# 130802_AriloRX_0_0.net
KiCad netlist of a schematic drawn in EAGLE
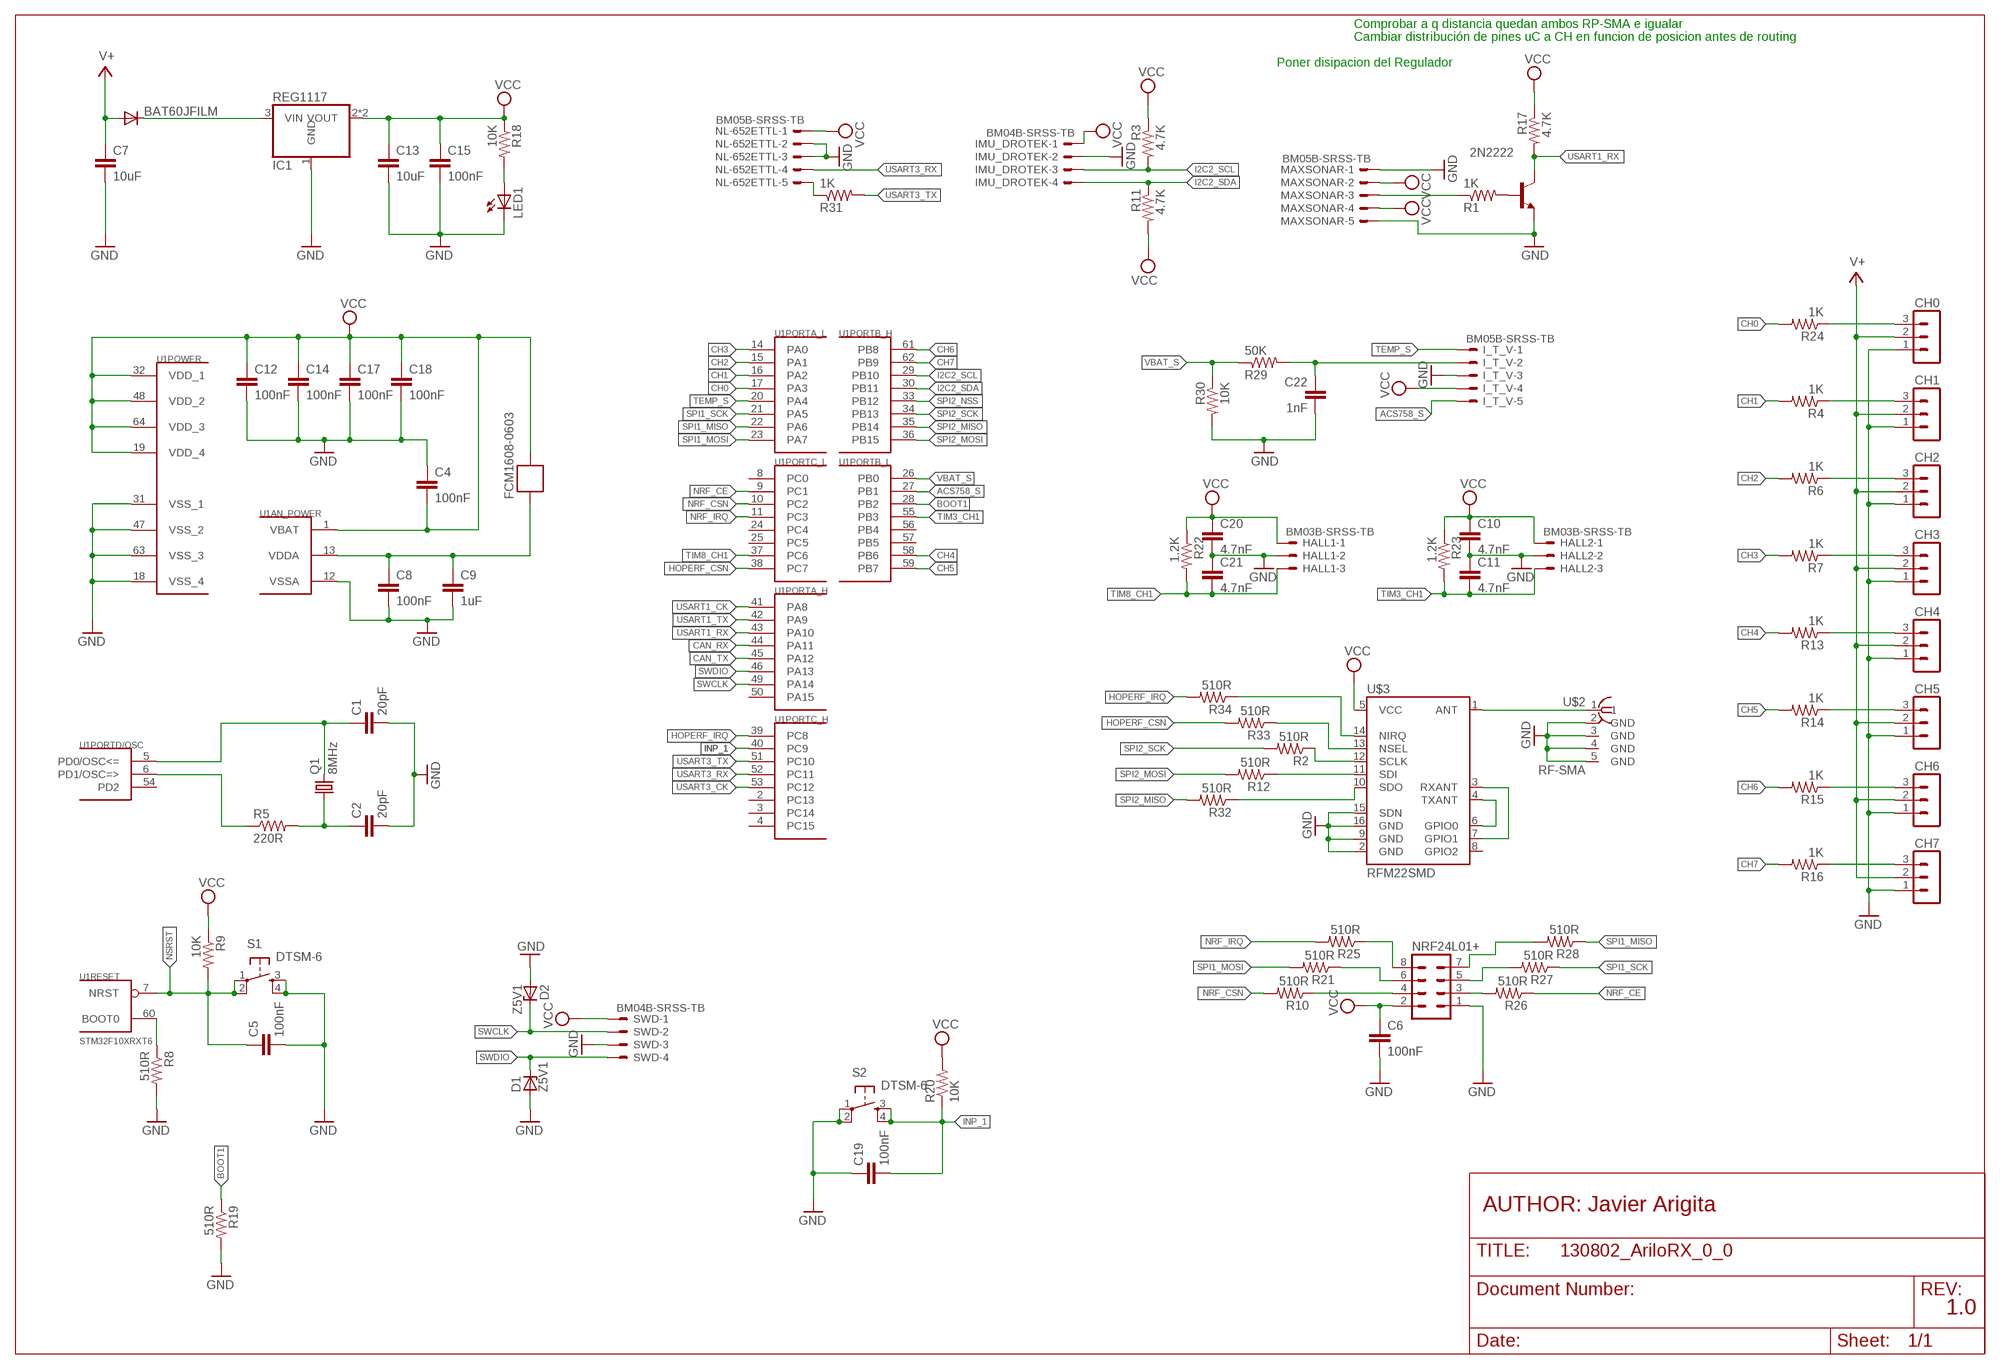
[diagram p0: schematic, sheet 1]

(export (version "E")
  (design (tool "Eeschema 10.0.6"))
  (components
    (comp (ref "2N2222")
      (value "MMBT2222ALT1-NPN-SOT23-BEC")
      (footprint "eagle-import:SOT23-BEC")
      (libsource (lib "eagle-import") (part "-NPN-SOT23-BECMMBT2222ALT1"))
    )
    (comp (ref "BAT60JFILM")
      (value "DIODE-SOD323-R")
      (footprint "eagle-import:SOD323-R")
      (libsource (lib "eagle-import") (part "DIODE-SOD323-R"))
    )
    (comp (ref "C1")
      (value "20pF")
      (footprint "eagle-import:C0805")
      (libsource (lib "eagle-import") (part "C-EUC0805"))
    )
    (comp (ref "C2")
      (value "20pF")
      (footprint "eagle-import:C0805")
      (libsource (lib "eagle-import") (part "C-EUC0805"))
    )
    (comp (ref "C4")
      (value "100nF")
      (footprint "eagle-import:C0805")
      (libsource (lib "eagle-import") (part "C-EUC0805"))
    )
    (comp (ref "C5")
      (value "100nF")
      (footprint "eagle-import:C0805")
      (libsource (lib "eagle-import") (part "C-EUC0805"))
    )
    (comp (ref "C6")
      (value "100nF")
      (footprint "eagle-import:C0805")
      (libsource (lib "eagle-import") (part "C-EUC0805"))
    )
    (comp (ref "C7")
      (value "10uF")
      (footprint "eagle-import:C3216")
      (libsource (lib "eagle-import") (part "resistor_C-EUC3216"))
    )
    (comp (ref "C8")
      (value "100nF")
      (footprint "eagle-import:C0805")
      (libsource (lib "eagle-import") (part "C-EUC0805"))
    )
    (comp (ref "C9")
      (value "1uF")
      (footprint "eagle-import:C3216")
      (libsource (lib "eagle-import") (part "resistor_C-EUC3216"))
    )
    (comp (ref "C10")
      (value "4.7nF")
      (footprint "eagle-import:C0805")
      (libsource (lib "eagle-import") (part "C-EUC0805"))
    )
    (comp (ref "C11")
      (value "4.7nF")
      (footprint "eagle-import:C0805")
      (libsource (lib "eagle-import") (part "C-EUC0805"))
    )
    (comp (ref "C12")
      (value "100nF")
      (footprint "eagle-import:C0805")
      (libsource (lib "eagle-import") (part "C-EUC0805"))
    )
    (comp (ref "C13")
      (value "10uF")
      (footprint "eagle-import:C3216")
      (libsource (lib "eagle-import") (part "resistor_C-EUC3216"))
    )
    (comp (ref "C14")
      (value "100nF")
      (footprint "eagle-import:C0805")
      (libsource (lib "eagle-import") (part "C-EUC0805"))
    )
    (comp (ref "C15")
      (value "100nF")
      (footprint "eagle-import:C0805")
      (libsource (lib "eagle-import") (part "C-EUC0805"))
    )
    (comp (ref "C17")
      (value "100nF")
      (footprint "eagle-import:C0805")
      (libsource (lib "eagle-import") (part "C-EUC0805"))
    )
    (comp (ref "C18")
      (value "100nF")
      (footprint "eagle-import:C0805")
      (libsource (lib "eagle-import") (part "C-EUC0805"))
    )
    (comp (ref "C19")
      (value "100nF")
      (footprint "eagle-import:C0805")
      (libsource (lib "eagle-import") (part "C-EUC0805"))
    )
    (comp (ref "C20")
      (value "4.7nF")
      (footprint "eagle-import:C0805")
      (libsource (lib "eagle-import") (part "C-EUC0805"))
    )
    (comp (ref "C21")
      (value "4.7nF")
      (footprint "eagle-import:C0805")
      (libsource (lib "eagle-import") (part "C-EUC0805"))
    )
    (comp (ref "C22")
      (value "1nF")
      (footprint "eagle-import:C0805")
      (libsource (lib "eagle-import") (part "C-EUC0805"))
    )
    (comp (ref "CH0")
      (value "MA03-1")
      (footprint "eagle-import:MA03-1")
      (libsource (lib "eagle-import") (part "MA03-1"))
    )
    (comp (ref "CH1")
      (value "MA03-1")
      (footprint "eagle-import:MA03-1")
      (libsource (lib "eagle-import") (part "MA03-1"))
    )
    (comp (ref "CH2")
      (value "MA03-1")
      (footprint "eagle-import:MA03-1")
      (libsource (lib "eagle-import") (part "MA03-1"))
    )
    (comp (ref "CH3")
      (value "MA03-1")
      (footprint "eagle-import:MA03-1")
      (libsource (lib "eagle-import") (part "MA03-1"))
    )
    (comp (ref "CH4")
      (value "MA03-1")
      (footprint "eagle-import:MA03-1")
      (libsource (lib "eagle-import") (part "MA03-1"))
    )
    (comp (ref "CH5")
      (value "MA03-1")
      (footprint "eagle-import:MA03-1")
      (libsource (lib "eagle-import") (part "MA03-1"))
    )
    (comp (ref "CH6")
      (value "MA03-1")
      (footprint "eagle-import:MA03-1")
      (libsource (lib "eagle-import") (part "MA03-1"))
    )
    (comp (ref "CH7")
      (value "MA03-1")
      (footprint "eagle-import:MA03-1")
      (libsource (lib "eagle-import") (part "MA03-1"))
    )
    (comp (ref "D1")
      (value "Z5V1")
      (footprint "eagle-import:SOD80C")
      (libsource (lib "eagle-import") (part "ZENER-DIODESOD80C"))
    )
    (comp (ref "D2")
      (value "Z5V1")
      (footprint "eagle-import:SOD80C")
      (libsource (lib "eagle-import") (part "ZENER-DIODESOD80C"))
    )
    (comp (ref "FCM1608-0603")
      (value "FERRITE-BEAD")
      (footprint "eagle-import:R0603")
      (libsource (lib "eagle-import") (part "FERRITE-BEAD"))
    )
    (comp (ref "HALL1")
      (value "BM03B-SRSS-TB")
      (footprint "eagle-import:BM03B-SRSS-TB")
      (libsource (lib "eagle-import") (part "?M03B-SRSS-TBB"))
    )
    (comp (ref "HALL2")
      (value "BM03B-SRSS-TB")
      (footprint "eagle-import:BM03B-SRSS-TB")
      (libsource (lib "eagle-import") (part "?M03B-SRSS-TBB"))
    )
    (comp (ref "IC1")
      (value "REG1117")
      (footprint "eagle-import:SOT223")
      (libsource (lib "eagle-import") (part "REG1117"))
    )
    (comp (ref "IMU_DROTEK")
      (value "BM04B-SRSS-TB")
      (footprint "eagle-import:BM04B-SRSS-TB")
      (libsource (lib "eagle-import") (part "?M04B-SRSS-TBB"))
    )
    (comp (ref "I_T_V")
      (value "BM05B-SRSS-TB")
      (footprint "eagle-import:BM05B-SRSS-TB")
      (libsource (lib "eagle-import") (part "?M05B-SRSS-TBB"))
    )
    (comp (ref "LED1")
      (value "LED0805")
      (footprint "eagle-import:CHIPLED_0805")
      (libsource (lib "eagle-import") (part "LED0805"))
    )
    (comp (ref "MAXSONAR")
      (value "BM05B-SRSS-TB")
      (footprint "eagle-import:BM05B-SRSS-TB")
      (libsource (lib "eagle-import") (part "?M05B-SRSS-TBB"))
    )
    (comp (ref "NL-652ETTL")
      (value "BM05B-SRSS-TB")
      (footprint "eagle-import:BM05B-SRSS-TB")
      (libsource (lib "eagle-import") (part "?M05B-SRSS-TBB"))
    )
    (comp (ref "NRF24L01+")
      (value "MA04-2")
      (footprint "eagle-import:MA04-2")
      (libsource (lib "eagle-import") (part "MA04-2"))
    )
    (comp (ref "Q1")
      (value "8MHz")
      (footprint "eagle-import:SM49")
      (libsource (lib "eagle-import") (part "CRYSTALSM49"))
    )
    (comp (ref "R1")
      (value "1K")
      (footprint "eagle-import:R0805")
      (libsource (lib "eagle-import") (part "RESISTOR0805"))
    )
    (comp (ref "R2")
      (value "510R")
      (footprint "eagle-import:R0805")
      (libsource (lib "eagle-import") (part "RESISTOR0805"))
    )
    (comp (ref "R3")
      (value "4.7K")
      (footprint "eagle-import:R0805")
      (libsource (lib "eagle-import") (part "RESISTOR0805"))
    )
    (comp (ref "R4")
      (value "1K")
      (footprint "eagle-import:R0805")
      (libsource (lib "eagle-import") (part "RESISTOR0805"))
    )
    (comp (ref "R5")
      (value "220R")
      (footprint "eagle-import:R0805")
      (libsource (lib "eagle-import") (part "RESISTOR0805"))
    )
    (comp (ref "R6")
      (value "1K")
      (footprint "eagle-import:R0805")
      (libsource (lib "eagle-import") (part "RESISTOR0805"))
    )
    (comp (ref "R7")
      (value "1K")
      (footprint "eagle-import:R0805")
      (libsource (lib "eagle-import") (part "RESISTOR0805"))
    )
    (comp (ref "R8")
      (value "510R")
      (footprint "eagle-import:R0805")
      (libsource (lib "eagle-import") (part "RESISTOR0805"))
    )
    (comp (ref "R9")
      (value "10K")
      (footprint "eagle-import:R0805")
      (libsource (lib "eagle-import") (part "RESISTOR0805"))
    )
    (comp (ref "R10")
      (value "510R")
      (footprint "eagle-import:R0805")
      (libsource (lib "eagle-import") (part "RESISTOR0805"))
    )
    (comp (ref "R11")
      (value "4.7K")
      (footprint "eagle-import:R0805")
      (libsource (lib "eagle-import") (part "RESISTOR0805"))
    )
    (comp (ref "R12")
      (value "510R")
      (footprint "eagle-import:R0805")
      (libsource (lib "eagle-import") (part "RESISTOR0805"))
    )
    (comp (ref "R13")
      (value "1K")
      (footprint "eagle-import:R0805")
      (libsource (lib "eagle-import") (part "RESISTOR0805"))
    )
    (comp (ref "R14")
      (value "1K")
      (footprint "eagle-import:R0805")
      (libsource (lib "eagle-import") (part "RESISTOR0805"))
    )
    (comp (ref "R15")
      (value "1K")
      (footprint "eagle-import:R0805")
      (libsource (lib "eagle-import") (part "RESISTOR0805"))
    )
    (comp (ref "R16")
      (value "1K")
      (footprint "eagle-import:R0805")
      (libsource (lib "eagle-import") (part "RESISTOR0805"))
    )
    (comp (ref "R17")
      (value "4.7K")
      (footprint "eagle-import:R0805")
      (libsource (lib "eagle-import") (part "RESISTOR0805"))
    )
    (comp (ref "R18")
      (value "10K")
      (footprint "eagle-import:R0805")
      (libsource (lib "eagle-import") (part "RESISTOR0805"))
    )
    (comp (ref "R19")
      (value "510R")
      (footprint "eagle-import:R0805")
      (libsource (lib "eagle-import") (part "RESISTOR0805"))
    )
    (comp (ref "R20")
      (value "10K")
      (footprint "eagle-import:R0805")
      (libsource (lib "eagle-import") (part "RESISTOR0805"))
    )
    (comp (ref "R21")
      (value "510R")
      (footprint "eagle-import:R0805")
      (libsource (lib "eagle-import") (part "RESISTOR0805"))
    )
    (comp (ref "R22")
      (value "1.2K")
      (footprint "eagle-import:R0805")
      (libsource (lib "eagle-import") (part "RESISTOR0805"))
    )
    (comp (ref "R23")
      (value "1.2K")
      (footprint "eagle-import:R0805")
      (libsource (lib "eagle-import") (part "RESISTOR0805"))
    )
    (comp (ref "R24")
      (value "1K")
      (footprint "eagle-import:R0805")
      (libsource (lib "eagle-import") (part "RESISTOR0805"))
    )
    (comp (ref "R25")
      (value "510R")
      (footprint "eagle-import:R0805")
      (libsource (lib "eagle-import") (part "RESISTOR0805"))
    )
    (comp (ref "R26")
      (value "510R")
      (footprint "eagle-import:R0805")
      (libsource (lib "eagle-import") (part "RESISTOR0805"))
    )
    (comp (ref "R27")
      (value "510R")
      (footprint "eagle-import:R0805")
      (libsource (lib "eagle-import") (part "RESISTOR0805"))
    )
    (comp (ref "R28")
      (value "510R")
      (footprint "eagle-import:R0805")
      (libsource (lib "eagle-import") (part "RESISTOR0805"))
    )
    (comp (ref "R29")
      (value "50K")
      (footprint "eagle-import:R0805")
      (libsource (lib "eagle-import") (part "RESISTOR0805"))
    )
    (comp (ref "R30")
      (value "10K")
      (footprint "eagle-import:R0805")
      (libsource (lib "eagle-import") (part "RESISTOR0805"))
    )
    (comp (ref "R31")
      (value "1K")
      (footprint "eagle-import:R0805")
      (libsource (lib "eagle-import") (part "RESISTOR0805"))
    )
    (comp (ref "R32")
      (value "510R")
      (footprint "eagle-import:R0805")
      (libsource (lib "eagle-import") (part "RESISTOR0805"))
    )
    (comp (ref "R33")
      (value "510R")
      (footprint "eagle-import:R0805")
      (libsource (lib "eagle-import") (part "RESISTOR0805"))
    )
    (comp (ref "R34")
      (value "510R")
      (footprint "eagle-import:R0805")
      (libsource (lib "eagle-import") (part "RESISTOR0805"))
    )
    (comp (ref "S1")
      (value "DTSM-6")
      (footprint "eagle-import:DTSM-6")
      (libsource (lib "eagle-import") (part "DTSM-6"))
    )
    (comp (ref "S2")
      (value "DTSM-6")
      (footprint "eagle-import:DTSM-6")
      (libsource (lib "eagle-import") (part "DTSM-6"))
    )
    (comp (ref "SWD")
      (value "BM04B-SRSS-TB")
      (footprint "eagle-import:BM04B-SRSS-TB")
      (libsource (lib "eagle-import") (part "?M04B-SRSS-TBB"))
    )
    (comp (ref "U$2")
      (value "RF-SMA")
      (footprint "eagle-import:BU-SMA-H")
      (libsource (lib "eagle-import") (part "RF-SMA"))
    )
    (comp (ref "U$3")
      (value "RFM22SMD")
      (footprint "eagle-import:RFM22-XXX-S2")
      (libsource (lib "eagle-import") (part "RFM22SMD"))
    )
    (comp (ref "U1")
      (value "STM32F10XRXT6")
      (footprint "eagle-import:TQFP64")
      (libsource (lib "eagle-import") (part "STM32F10XRXT6"))
    )
  )
  (nets
    (net (code "1") (name "ACS758_S") (class "Default")
      (node (ref "I_T_V") (pin "5") (pinfunction "S_5") (pintype "passive"))
      (node (ref "U1") (pin "27") (pinfunction "PB1_27") (pintype "bidirectional"))
    )
    (net (code "2") (name "BOOT1") (class "Default")
      (node (ref "R19") (pin "1") (pinfunction "1_1") (pintype "passive"))
      (node (ref "U1") (pin "28") (pinfunction "PB2_28") (pintype "bidirectional"))
    )
    (net (code "3") (name "CAN_RX") (class "Default")
      (node (ref "U1") (pin "44") (pinfunction "PA11_44") (pintype "bidirectional"))
    )
    (net (code "4") (name "CAN_TX") (class "Default")
      (node (ref "U1") (pin "45") (pinfunction "PA12_45") (pintype "bidirectional"))
    )
    (net (code "5") (name "CH0") (class "Default")
      (node (ref "R24") (pin "2") (pinfunction "2_2") (pintype "passive"))
      (node (ref "U1") (pin "17") (pinfunction "PA3_17") (pintype "bidirectional"))
    )
    (net (code "6") (name "CH1") (class "Default")
      (node (ref "R4") (pin "2") (pinfunction "2_2") (pintype "passive"))
      (node (ref "U1") (pin "16") (pinfunction "PA2_16") (pintype "bidirectional"))
    )
    (net (code "7") (name "CH2") (class "Default")
      (node (ref "R6") (pin "2") (pinfunction "2_2") (pintype "passive"))
      (node (ref "U1") (pin "15") (pinfunction "PA1_15") (pintype "bidirectional"))
    )
    (net (code "8") (name "CH3") (class "Default")
      (node (ref "R7") (pin "2") (pinfunction "2_2") (pintype "passive"))
      (node (ref "U1") (pin "14") (pinfunction "PA0_14") (pintype "bidirectional"))
    )
    (net (code "9") (name "CH4") (class "Default")
      (node (ref "R13") (pin "2") (pinfunction "2_2") (pintype "passive"))
      (node (ref "U1") (pin "58") (pinfunction "PB6_58") (pintype "bidirectional"))
    )
    (net (code "10") (name "CH5") (class "Default")
      (node (ref "R14") (pin "2") (pinfunction "2_2") (pintype "passive"))
      (node (ref "U1") (pin "59") (pinfunction "PB7_59") (pintype "bidirectional"))
    )
    (net (code "11") (name "CH6") (class "Default")
      (node (ref "R15") (pin "2") (pinfunction "2_2") (pintype "passive"))
      (node (ref "U1") (pin "61") (pinfunction "PB8_61") (pintype "bidirectional"))
    )
    (net (code "12") (name "CH7") (class "Default")
      (node (ref "R16") (pin "2") (pinfunction "2_2") (pintype "passive"))
      (node (ref "U1") (pin "62") (pinfunction "PB9_62") (pintype "bidirectional"))
    )
    (net (code "13") (name "GND") (class "Default")
      (node (ref "2N2222") (pin "E") (pinfunction "E_E") (pintype "passive"))
      (node (ref "C1") (pin "2") (pinfunction "2_2") (pintype "passive"))
      (node (ref "C10") (pin "2") (pinfunction "2_2") (pintype "passive"))
      (node (ref "C11") (pin "1") (pinfunction "1_1") (pintype "passive"))
      (node (ref "C12") (pin "2") (pinfunction "2_2") (pintype "passive"))
      (node (ref "C13") (pin "2") (pinfunction "2_2") (pintype "passive"))
      (node (ref "C14") (pin "2") (pinfunction "2_2") (pintype "passive"))
      (node (ref "C15") (pin "2") (pinfunction "2_2") (pintype "passive"))
      (node (ref "C17") (pin "2") (pinfunction "2_2") (pintype "passive"))
      (node (ref "C18") (pin "2") (pinfunction "2_2") (pintype "passive"))
      (node (ref "C19") (pin "1") (pinfunction "1_1") (pintype "passive"))
      (node (ref "C2") (pin "2") (pinfunction "2_2") (pintype "passive"))
      (node (ref "C20") (pin "2") (pinfunction "2_2") (pintype "passive"))
      (node (ref "C21") (pin "1") (pinfunction "1_1") (pintype "passive"))
      (node (ref "C22") (pin "2") (pinfunction "2_2") (pintype "passive"))
      (node (ref "C4") (pin "1") (pinfunction "1_1") (pintype "passive"))
      (node (ref "C5") (pin "2") (pinfunction "2_2") (pintype "passive"))
      (node (ref "C6") (pin "2") (pinfunction "2_2") (pintype "passive"))
      (node (ref "C7") (pin "2") (pinfunction "2_2") (pintype "passive"))
      (node (ref "C8") (pin "2") (pinfunction "2_2") (pintype "passive"))
      (node (ref "C9") (pin "2") (pinfunction "2_2") (pintype "passive"))
      (node (ref "CH0") (pin "1") (pinfunction "1_1") (pintype "passive"))
      (node (ref "CH1") (pin "1") (pinfunction "1_1") (pintype "passive"))
      (node (ref "CH2") (pin "1") (pinfunction "1_1") (pintype "passive"))
      (node (ref "CH3") (pin "1") (pinfunction "1_1") (pintype "passive"))
      (node (ref "CH4") (pin "1") (pinfunction "1_1") (pintype "passive"))
      (node (ref "CH5") (pin "1") (pinfunction "1_1") (pintype "passive"))
      (node (ref "CH6") (pin "1") (pinfunction "1_1") (pintype "passive"))
      (node (ref "CH7") (pin "1") (pinfunction "1_1") (pintype "passive"))
      (node (ref "D1") (pin "A") (pinfunction "A_A") (pintype "passive"))
      (node (ref "D2") (pin "A") (pinfunction "A_A") (pintype "passive"))
      (node (ref "HALL1") (pin "2") (pinfunction "S_2") (pintype "passive"))
      (node (ref "HALL2") (pin "2") (pinfunction "S_2") (pintype "passive"))
      (node (ref "IC1") (pin "1") (pinfunction "GND_1") (pintype "power_in"))
      (node (ref "IMU_DROTEK") (pin "2") (pinfunction "S_2") (pintype "passive"))
      (node (ref "I_T_V") (pin "3") (pinfunction "S_3") (pintype "passive"))
      (node (ref "LED1") (pin "C") (pinfunction "C_C") (pintype "passive"))
      (node (ref "MAXSONAR") (pin "1") (pinfunction "S_1") (pintype "passive"))
      (node (ref "MAXSONAR") (pin "5") (pinfunction "S_5") (pintype "passive"))
      (node (ref "NL-652ETTL") (pin "2") (pinfunction "S_2") (pintype "passive"))
      (node (ref "NL-652ETTL") (pin "3") (pinfunction "S_3") (pintype "passive"))
      (node (ref "NRF24L01+") (pin "1") (pinfunction "1_1") (pintype "passive"))
      (node (ref "R19") (pin "2") (pinfunction "2_2") (pintype "passive"))
      (node (ref "R30") (pin "2") (pinfunction "2_2") (pintype "passive"))
      (node (ref "R8") (pin "2") (pinfunction "2_2") (pintype "passive"))
      (node (ref "S1") (pin "3") (pinfunction "3_3") (pintype "passive"))
      (node (ref "S1") (pin "4") (pinfunction "4_4") (pintype "passive"))
      (node (ref "S2") (pin "1") (pinfunction "1_1") (pintype "passive"))
      (node (ref "S2") (pin "2") (pinfunction "2_2") (pintype "passive"))
      (node (ref "SWD") (pin "3") (pinfunction "S_3") (pintype "passive"))
      (node (ref "U$2") (pin "2") (pinfunction "GND_2") (pintype "power_in"))
      (node (ref "U$2") (pin "3") (pinfunction "GND_3") (pintype "bidirectional"))
      (node (ref "U$2") (pin "4") (pinfunction "GND_4") (pintype "bidirectional"))
      (node (ref "U$2") (pin "5") (pinfunction "GND_5") (pintype "bidirectional"))
      (node (ref "U$3") (pin "15") (pinfunction "SDN_15") (pintype "input"))
      (node (ref "U$3") (pin "16") (pinfunction "GND_16") (pintype "power_in"))
      (node (ref "U$3") (pin "2") (pinfunction "GND_2") (pintype "power_in"))
      (node (ref "U$3") (pin "9") (pinfunction "GND_9") (pintype "power_in"))
      (node (ref "U1") (pin "12") (pinfunction "VSSA_12") (pintype "power_in"))
      (node (ref "U1") (pin "18") (pinfunction "VSS_4_18") (pintype "power_in"))
      (node (ref "U1") (pin "31") (pinfunction "VSS_1_31") (pintype "power_in"))
      (node (ref "U1") (pin "47") (pinfunction "VSS_2_47") (pintype "power_in"))
      (node (ref "U1") (pin "63") (pinfunction "VSS_3_63") (pintype "power_in"))
    )
    (net (code "14") (name "HOPERF_CSN") (class "Default")
      (node (ref "R33") (pin "2") (pinfunction "2_2") (pintype "passive"))
      (node (ref "U1") (pin "38") (pinfunction "PC7_38") (pintype "bidirectional"))
    )
    (net (code "15") (name "HOPERF_IRQ") (class "Default")
      (node (ref "R34") (pin "2") (pinfunction "2_2") (pintype "passive"))
      (node (ref "U1") (pin "39") (pinfunction "PC8_39") (pintype "bidirectional"))
    )
    (net (code "16") (name "I2C2_SCL") (class "Default")
      (node (ref "IMU_DROTEK") (pin "3") (pinfunction "S_3") (pintype "passive"))
      (node (ref "R3") (pin "2") (pinfunction "2_2") (pintype "passive"))
      (node (ref "U1") (pin "29") (pinfunction "PB10_29") (pintype "bidirectional"))
    )
    (net (code "17") (name "I2C2_SDA") (class "Default")
      (node (ref "IMU_DROTEK") (pin "4") (pinfunction "S_4") (pintype "passive"))
      (node (ref "R11") (pin "1") (pinfunction "1_1") (pintype "passive"))
      (node (ref "U1") (pin "30") (pinfunction "PB11_30") (pintype "bidirectional"))
    )
    (net (code "18") (name "INP_1") (class "Default")
      (node (ref "C19") (pin "2") (pinfunction "2_2") (pintype "passive"))
      (node (ref "R20") (pin "1") (pinfunction "1_1") (pintype "passive"))
      (node (ref "S2") (pin "3") (pinfunction "3_3") (pintype "passive"))
      (node (ref "S2") (pin "4") (pinfunction "4_4") (pintype "passive"))
      (node (ref "U1") (pin "40") (pinfunction "PC9_40") (pintype "bidirectional"))
    )
    (net (code "19") (name "NRF_CE") (class "Default")
      (node (ref "R26") (pin "1") (pinfunction "1_1") (pintype "passive"))
      (node (ref "U1") (pin "9") (pinfunction "PC1_9") (pintype "bidirectional"))
    )
    (net (code "20") (name "NRF_CSN") (class "Default")
      (node (ref "R10") (pin "2") (pinfunction "2_2") (pintype "passive"))
      (node (ref "U1") (pin "10") (pinfunction "PC2_10") (pintype "bidirectional"))
    )
    (net (code "21") (name "NRF_IRQ") (class "Default")
      (node (ref "R25") (pin "2") (pinfunction "2_2") (pintype "passive"))
      (node (ref "U1") (pin "11") (pinfunction "PC3_11") (pintype "bidirectional"))
    )
    (net (code "22") (name "NSRST") (class "Default")
      (node (ref "C5") (pin "1") (pinfunction "1_1") (pintype "passive"))
      (node (ref "R9") (pin "2") (pinfunction "2_2") (pintype "passive"))
      (node (ref "S1") (pin "1") (pinfunction "1_1") (pintype "passive"))
      (node (ref "S1") (pin "2") (pinfunction "2_2") (pintype "passive"))
      (node (ref "U1") (pin "7") (pinfunction "NRST_7") (pintype "input"))
    )
    (net (code "23") (name "Net-(2N2222-PadB)") (class "Default")
      (node (ref "2N2222") (pin "B") (pinfunction "B_B") (pintype "passive"))
      (node (ref "R1") (pin "2") (pinfunction "2_2") (pintype "passive"))
    )
    (net (code "24") (name "Net-(C2-Pad1)") (class "Default")
      (node (ref "C2") (pin "1") (pinfunction "1_1") (pintype "passive"))
      (node (ref "Q1") (pin "1") (pinfunction "1_1") (pintype "passive"))
      (node (ref "R5") (pin "2") (pinfunction "2_2") (pintype "passive"))
    )
    (net (code "25") (name "Net-(CH0-Pad3)") (class "Default")
      (node (ref "CH0") (pin "3") (pinfunction "3_3") (pintype "passive"))
      (node (ref "R24") (pin "1") (pinfunction "1_1") (pintype "passive"))
    )
    (net (code "26") (name "Net-(CH1-Pad3)") (class "Default")
      (node (ref "CH1") (pin "3") (pinfunction "3_3") (pintype "passive"))
      (node (ref "R4") (pin "1") (pinfunction "1_1") (pintype "passive"))
    )
    (net (code "27") (name "Net-(CH2-Pad3)") (class "Default")
      (node (ref "CH2") (pin "3") (pinfunction "3_3") (pintype "passive"))
      (node (ref "R6") (pin "1") (pinfunction "1_1") (pintype "passive"))
    )
    (net (code "28") (name "Net-(CH3-Pad3)") (class "Default")
      (node (ref "CH3") (pin "3") (pinfunction "3_3") (pintype "passive"))
      (node (ref "R7") (pin "1") (pinfunction "1_1") (pintype "passive"))
    )
    (net (code "29") (name "Net-(CH4-Pad3)") (class "Default")
      (node (ref "CH4") (pin "3") (pinfunction "3_3") (pintype "passive"))
      (node (ref "R13") (pin "1") (pinfunction "1_1") (pintype "passive"))
    )
    (net (code "30") (name "Net-(CH5-Pad3)") (class "Default")
      (node (ref "CH5") (pin "3") (pinfunction "3_3") (pintype "passive"))
      (node (ref "R14") (pin "1") (pinfunction "1_1") (pintype "passive"))
    )
    (net (code "31") (name "Net-(CH6-Pad3)") (class "Default")
      (node (ref "CH6") (pin "3") (pinfunction "3_3") (pintype "passive"))
      (node (ref "R15") (pin "1") (pinfunction "1_1") (pintype "passive"))
    )
    (net (code "32") (name "Net-(CH7-Pad3)") (class "Default")
      (node (ref "CH7") (pin "3") (pinfunction "3_3") (pintype "passive"))
      (node (ref "R16") (pin "1") (pinfunction "1_1") (pintype "passive"))
    )
    (net (code "33") (name "Net-(FCM1608-0603-P$2)") (class "Default")
      (node (ref "C8") (pin "1") (pinfunction "1_1") (pintype "passive"))
      (node (ref "C9") (pin "1") (pinfunction "1_1") (pintype "passive"))
      (node (ref "FCM1608-0603") (pin "2") (pinfunction "P$2_2") (pintype "bidirectional"))
      (node (ref "U1") (pin "13") (pinfunction "VDDA_13") (pintype "power_in"))
    )
    (net (code "34") (name "Net-(IC1-VIN)") (class "Default")
      (node (ref "BAT60JFILM") (pin "C") (pinfunction "C_C") (pintype "passive"))
      (node (ref "IC1") (pin "3") (pinfunction "VIN_3") (pintype "input"))
    )
    (net (code "35") (name "Net-(I_T_VB-S)") (class "Default")
      (node (ref "C22") (pin "1") (pinfunction "1_1") (pintype "passive"))
      (node (ref "I_T_V") (pin "2") (pinfunction "S_2") (pintype "passive"))
      (node (ref "R29") (pin "2") (pinfunction "2_2") (pintype "passive"))
    )
    (net (code "36") (name "Net-(LED1-PadA)") (class "Default")
      (node (ref "LED1") (pin "A") (pinfunction "A_A") (pintype "passive"))
      (node (ref "R18") (pin "2") (pinfunction "2_2") (pintype "passive"))
    )
    (net (code "37") (name "Net-(MAXSONARC-S)") (class "Default")
      (node (ref "MAXSONAR") (pin "3") (pinfunction "S_3") (pintype "passive"))
      (node (ref "R1") (pin "1") (pinfunction "1_1") (pintype "passive"))
    )
    (net (code "38") (name "Net-(NL-652ETTLE-S)") (class "Default")
      (node (ref "NL-652ETTL") (pin "5") (pinfunction "S_5") (pintype "passive"))
      (node (ref "R31") (pin "1") (pinfunction "1_1") (pintype "passive"))
    )
    (net (code "39") (name "Net-(NRF24L01+-Pad3)") (class "Default")
      (node (ref "NRF24L01+") (pin "3") (pinfunction "3_3") (pintype "passive"))
      (node (ref "R26") (pin "2") (pinfunction "2_2") (pintype "passive"))
    )
    (net (code "40") (name "Net-(NRF24L01+-Pad4)") (class "Default")
      (node (ref "NRF24L01+") (pin "4") (pinfunction "4_4") (pintype "passive"))
      (node (ref "R10") (pin "1") (pinfunction "1_1") (pintype "passive"))
    )
    (net (code "41") (name "Net-(NRF24L01+-Pad5)") (class "Default")
      (node (ref "NRF24L01+") (pin "5") (pinfunction "5_5") (pintype "passive"))
      (node (ref "R27") (pin "2") (pinfunction "2_2") (pintype "passive"))
    )
    (net (code "42") (name "Net-(NRF24L01+-Pad6)") (class "Default")
      (node (ref "NRF24L01+") (pin "6") (pinfunction "6_6") (pintype "passive"))
      (node (ref "R21") (pin "1") (pinfunction "1_1") (pintype "passive"))
    )
    (net (code "43") (name "Net-(NRF24L01+-Pad7)") (class "Default")
      (node (ref "NRF24L01+") (pin "7") (pinfunction "7_7") (pintype "passive"))
      (node (ref "R28") (pin "2") (pinfunction "2_2") (pintype "passive"))
    )
    (net (code "44") (name "Net-(NRF24L01+-Pad8)") (class "Default")
      (node (ref "NRF24L01+") (pin "8") (pinfunction "8_8") (pintype "passive"))
      (node (ref "R25") (pin "1") (pinfunction "1_1") (pintype "passive"))
    )
    (net (code "45") (name "Net-(U$3-ANT)") (class "Default")
      (node (ref "U$2") (pin "1") (pinfunction "1_1") (pintype "passive"))
      (node (ref "U$3") (pin "1") (pinfunction "ANT_1") (pintype "bidirectional"))
    )
    (net (code "46") (name "Net-(U$3-GPIO0)") (class "Default")
      (node (ref "U$3") (pin "4") (pinfunction "TXANT_4") (pintype "input"))
      (node (ref "U$3") (pin "6") (pinfunction "GPIO0_6") (pintype "bidirectional"))
    )
    (net (code "47") (name "Net-(U$3-GPIO1)") (class "Default")
      (node (ref "U$3") (pin "3") (pinfunction "RXANT_3") (pintype "input"))
      (node (ref "U$3") (pin "7") (pinfunction "GPIO1_7") (pintype "bidirectional"))
    )
    (net (code "48") (name "Net-(U$3-NIRQ)") (class "Default")
      (node (ref "R34") (pin "1") (pinfunction "1_1") (pintype "passive"))
      (node (ref "U$3") (pin "14") (pinfunction "NIRQ_14") (pintype "output"))
    )
    (net (code "49") (name "Net-(U$3-NSEL)") (class "Default")
      (node (ref "R33") (pin "1") (pinfunction "1_1") (pintype "passive"))
      (node (ref "U$3") (pin "13") (pinfunction "NSEL_13") (pintype "input"))
    )
    (net (code "50") (name "Net-(U$3-SCLK)") (class "Default")
      (node (ref "R2") (pin "1") (pinfunction "1_1") (pintype "passive"))
      (node (ref "U$3") (pin "12") (pinfunction "SCLK_12") (pintype "input"))
    )
    (net (code "51") (name "Net-(U$3-SDI)") (class "Default")
      (node (ref "R12") (pin "1") (pinfunction "1_1") (pintype "passive"))
      (node (ref "U$3") (pin "11") (pinfunction "SDI_11") (pintype "input"))
    )
    (net (code "52") (name "Net-(U$3-SDO)") (class "Default")
      (node (ref "R32") (pin "1") (pinfunction "1_1") (pintype "passive"))
      (node (ref "U$3") (pin "10") (pinfunction "SDO_10") (pintype "output"))
    )
    (net (code "53") (name "Net-(U1H-PD0{slash}OSC<=)") (class "Default")
      (node (ref "C1") (pin "1") (pinfunction "1_1") (pintype "passive"))
      (node (ref "Q1") (pin "2") (pinfunction "2_2") (pintype "passive"))
      (node (ref "U1") (pin "5") (pinfunction "PD0/OSC<=_5") (pintype "bidirectional"))
    )
    (net (code "54") (name "Net-(U1H-PD1{slash}OSC=>)") (class "Default")
      (node (ref "R5") (pin "1") (pinfunction "1_1") (pintype "passive"))
      (node (ref "U1") (pin "6") (pinfunction "PD1/OSC=>_6") (pintype "bidirectional"))
    )
    (net (code "55") (name "Net-(U1J-BOOT0)") (class "Default")
      (node (ref "R8") (pin "1") (pinfunction "1_1") (pintype "passive"))
      (node (ref "U1") (pin "60") (pinfunction "BOOT0_60") (pintype "input"))
    )
    (net (code "56") (name "SPI1_MISO") (class "Default")
      (node (ref "R28") (pin "1") (pinfunction "1_1") (pintype "passive"))
      (node (ref "U1") (pin "22") (pinfunction "PA6_22") (pintype "bidirectional"))
    )
    (net (code "57") (name "SPI1_MOSI") (class "Default")
      (node (ref "R21") (pin "2") (pinfunction "2_2") (pintype "passive"))
      (node (ref "U1") (pin "23") (pinfunction "PA7_23") (pintype "bidirectional"))
    )
    (net (code "58") (name "SPI1_SCK") (class "Default")
      (node (ref "R27") (pin "1") (pinfunction "1_1") (pintype "passive"))
      (node (ref "U1") (pin "21") (pinfunction "PA5_21") (pintype "bidirectional"))
    )
    (net (code "59") (name "SPI2_MISO") (class "Default")
      (node (ref "R32") (pin "2") (pinfunction "2_2") (pintype "passive"))
      (node (ref "U1") (pin "35") (pinfunction "PB14_35") (pintype "bidirectional"))
    )
    (net (code "60") (name "SPI2_MOSI") (class "Default")
      (node (ref "R12") (pin "2") (pinfunction "2_2") (pintype "passive"))
      (node (ref "U1") (pin "36") (pinfunction "PB15_36") (pintype "bidirectional"))
    )
    (net (code "61") (name "SPI2_NSS") (class "Default")
      (node (ref "U1") (pin "33") (pinfunction "PB12_33") (pintype "bidirectional"))
    )
    (net (code "62") (name "SPI2_SCK") (class "Default")
      (node (ref "R2") (pin "2") (pinfunction "2_2") (pintype "passive"))
      (node (ref "U1") (pin "34") (pinfunction "PB13_34") (pintype "bidirectional"))
    )
    (net (code "63") (name "SWCLK") (class "Default")
      (node (ref "D2") (pin "C") (pinfunction "C_C") (pintype "passive"))
      (node (ref "SWD") (pin "2") (pinfunction "S_2") (pintype "passive"))
      (node (ref "U1") (pin "49") (pinfunction "PA14_49") (pintype "bidirectional"))
    )
    (net (code "64") (name "SWDIO") (class "Default")
      (node (ref "D1") (pin "C") (pinfunction "C_C") (pintype "passive"))
      (node (ref "SWD") (pin "4") (pinfunction "S_4") (pintype "passive"))
      (node (ref "U1") (pin "46") (pinfunction "PA13_46") (pintype "bidirectional"))
    )
    (net (code "65") (name "TEMP_S") (class "Default")
      (node (ref "I_T_V") (pin "1") (pinfunction "S_1") (pintype "passive"))
      (node (ref "U1") (pin "20") (pinfunction "PA4_20") (pintype "bidirectional"))
    )
    (net (code "66") (name "TIM3_CH1") (class "Default")
      (node (ref "C11") (pin "2") (pinfunction "2_2") (pintype "passive"))
      (node (ref "HALL2") (pin "3") (pinfunction "S_3") (pintype "passive"))
      (node (ref "R23") (pin "2") (pinfunction "2_2") (pintype "passive"))
      (node (ref "U1") (pin "55") (pinfunction "PB3_55") (pintype "bidirectional"))
    )
    (net (code "67") (name "TIM8_CH1") (class "Default")
      (node (ref "C21") (pin "2") (pinfunction "2_2") (pintype "passive"))
      (node (ref "HALL1") (pin "3") (pinfunction "S_3") (pintype "passive"))
      (node (ref "R22") (pin "2") (pinfunction "2_2") (pintype "passive"))
      (node (ref "U1") (pin "37") (pinfunction "PC6_37") (pintype "bidirectional"))
    )
    (net (code "68") (name "USART1_CK") (class "Default")
      (node (ref "U1") (pin "41") (pinfunction "PA8_41") (pintype "bidirectional"))
    )
    (net (code "69") (name "USART1_RX") (class "Default")
      (node (ref "2N2222") (pin "C") (pinfunction "C_C") (pintype "passive"))
      (node (ref "R17") (pin "2") (pinfunction "2_2") (pintype "passive"))
      (node (ref "U1") (pin "43") (pinfunction "PA10_43") (pintype "bidirectional"))
    )
    (net (code "70") (name "USART1_TX") (class "Default")
      (node (ref "U1") (pin "42") (pinfunction "PA9_42") (pintype "bidirectional"))
    )
    (net (code "71") (name "USART3_CK") (class "Default")
      (node (ref "U1") (pin "53") (pinfunction "PC12_53") (pintype "bidirectional"))
    )
    (net (code "72") (name "USART3_RX") (class "Default")
      (node (ref "NL-652ETTL") (pin "4") (pinfunction "S_4") (pintype "passive"))
      (node (ref "U1") (pin "52") (pinfunction "PC11_52") (pintype "bidirectional"))
    )
    (net (code "73") (name "USART3_TX") (class "Default")
      (node (ref "R31") (pin "2") (pinfunction "2_2") (pintype "passive"))
      (node (ref "U1") (pin "51") (pinfunction "PC10_51") (pintype "bidirectional"))
    )
    (net (code "74") (name "V+") (class "Default")
      (node (ref "BAT60JFILM") (pin "A") (pinfunction "A_A") (pintype "passive"))
      (node (ref "C7") (pin "1") (pinfunction "1_1") (pintype "passive"))
      (node (ref "CH0") (pin "2") (pinfunction "2_2") (pintype "passive"))
      (node (ref "CH1") (pin "2") (pinfunction "2_2") (pintype "passive"))
      (node (ref "CH2") (pin "2") (pinfunction "2_2") (pintype "passive"))
      (node (ref "CH3") (pin "2") (pinfunction "2_2") (pintype "passive"))
      (node (ref "CH4") (pin "2") (pinfunction "2_2") (pintype "passive"))
      (node (ref "CH5") (pin "2") (pinfunction "2_2") (pintype "passive"))
      (node (ref "CH6") (pin "2") (pinfunction "2_2") (pintype "passive"))
      (node (ref "CH7") (pin "2") (pinfunction "2_2") (pintype "passive"))
    )
    (net (code "75") (name "VBAT_S") (class "Default")
      (node (ref "R29") (pin "1") (pinfunction "1_1") (pintype "passive"))
      (node (ref "R30") (pin "1") (pinfunction "1_1") (pintype "passive"))
      (node (ref "U1") (pin "26") (pinfunction "PB0_26") (pintype "bidirectional"))
    )
    (net (code "76") (name "VCC") (class "Default")
      (node (ref "C10") (pin "1") (pinfunction "1_1") (pintype "passive"))
      (node (ref "C12") (pin "1") (pinfunction "1_1") (pintype "passive"))
      (node (ref "C13") (pin "1") (pinfunction "1_1") (pintype "passive"))
      (node (ref "C14") (pin "1") (pinfunction "1_1") (pintype "passive"))
      (node (ref "C15") (pin "1") (pinfunction "1_1") (pintype "passive"))
      (node (ref "C17") (pin "1") (pinfunction "1_1") (pintype "passive"))
      (node (ref "C18") (pin "1") (pinfunction "1_1") (pintype "passive"))
      (node (ref "C20") (pin "1") (pinfunction "1_1") (pintype "passive"))
      (node (ref "C4") (pin "2") (pinfunction "2_2") (pintype "passive"))
      (node (ref "C6") (pin "1") (pinfunction "1_1") (pintype "passive"))
      (node (ref "FCM1608-0603") (pin "1") (pinfunction "P$1_1") (pintype "bidirectional"))
      (node (ref "HALL1") (pin "1") (pinfunction "S_1") (pintype "passive"))
      (node (ref "HALL2") (pin "1") (pinfunction "S_1") (pintype "passive"))
      (node (ref "IC1") (pin "2") (pinfunction "VOUT_2") (pintype "power_in"))
      (node (ref "IC1") (pin "4") (pinfunction "VOUT_4") (pintype "power_in"))
      (node (ref "IMU_DROTEK") (pin "1") (pinfunction "S_1") (pintype "passive"))
      (node (ref "I_T_V") (pin "4") (pinfunction "S_4") (pintype "passive"))
      (node (ref "MAXSONAR") (pin "2") (pinfunction "S_2") (pintype "passive"))
      (node (ref "MAXSONAR") (pin "4") (pinfunction "S_4") (pintype "passive"))
      (node (ref "NL-652ETTL") (pin "1") (pinfunction "S_1") (pintype "passive"))
      (node (ref "NRF24L01+") (pin "2") (pinfunction "2_2") (pintype "passive"))
      (node (ref "R11") (pin "2") (pinfunction "2_2") (pintype "passive"))
      (node (ref "R17") (pin "1") (pinfunction "1_1") (pintype "passive"))
      (node (ref "R18") (pin "1") (pinfunction "1_1") (pintype "passive"))
      (node (ref "R20") (pin "2") (pinfunction "2_2") (pintype "passive"))
      (node (ref "R22") (pin "1") (pinfunction "1_1") (pintype "passive"))
      (node (ref "R23") (pin "1") (pinfunction "1_1") (pintype "passive"))
      (node (ref "R3") (pin "1") (pinfunction "1_1") (pintype "passive"))
      (node (ref "R9") (pin "1") (pinfunction "1_1") (pintype "passive"))
      (node (ref "SWD") (pin "1") (pinfunction "S_1") (pintype "passive"))
      (node (ref "U$3") (pin "5") (pinfunction "VCC_5") (pintype "bidirectional"))
      (node (ref "U1") (pin "1") (pinfunction "VBAT_1") (pintype "power_in"))
      (node (ref "U1") (pin "19") (pinfunction "VDD_4_19") (pintype "power_in"))
      (node (ref "U1") (pin "32") (pinfunction "VDD_1_32") (pintype "power_in"))
      (node (ref "U1") (pin "48") (pinfunction "VDD_2_48") (pintype "power_in"))
      (node (ref "U1") (pin "64") (pinfunction "VDD_3_64") (pintype "power_in"))
    )
    (net (code "77") (name "unconnected-(U$3-GPIO2-Pad8)") (class "Default")
      (node (ref "U$3") (pin "8") (pinfunction "GPIO2_8") (pintype "bidirectional"))
    )
    (net (code "78") (name "unconnected-(U1B-PA15-Pad50)") (class "Default")
      (node (ref "U1") (pin "50") (pinfunction "PA15_50") (pintype "bidirectional"))
    )
    (net (code "79") (name "unconnected-(U1E-PB4-Pad56)") (class "Default")
      (node (ref "U1") (pin "56") (pinfunction "PB4_56") (pintype "bidirectional"))
    )
    (net (code "80") (name "unconnected-(U1E-PB5-Pad57)") (class "Default")
      (node (ref "U1") (pin "57") (pinfunction "PB5_57") (pintype "bidirectional"))
    )
    (net (code "81") (name "unconnected-(U1F-PC13-Pad2)") (class "Default")
      (node (ref "U1") (pin "2") (pinfunction "PC13_2") (pintype "bidirectional"))
    )
    (net (code "82") (name "unconnected-(U1F-PC14-Pad3)") (class "Default")
      (node (ref "U1") (pin "3") (pinfunction "PC14_3") (pintype "bidirectional"))
    )
    (net (code "83") (name "unconnected-(U1F-PC15-Pad4)") (class "Default")
      (node (ref "U1") (pin "4") (pinfunction "PC15_4") (pintype "bidirectional"))
    )
    (net (code "84") (name "unconnected-(U1G-PC0-Pad8)") (class "Default")
      (node (ref "U1") (pin "8") (pinfunction "PC0_8") (pintype "bidirectional"))
    )
    (net (code "85") (name "unconnected-(U1G-PC4-Pad24)") (class "Default")
      (node (ref "U1") (pin "24") (pinfunction "PC4_24") (pintype "bidirectional"))
    )
    (net (code "86") (name "unconnected-(U1G-PC5-Pad25)") (class "Default")
      (node (ref "U1") (pin "25") (pinfunction "PC5_25") (pintype "bidirectional"))
    )
    (net (code "87") (name "unconnected-(U1H-PD2-Pad54)") (class "Default")
      (node (ref "U1") (pin "54") (pinfunction "PD2_54") (pintype "bidirectional"))
    )
  )
)
